# wifiaudiolink.net
KiCad netlist of a schematic drawn in EAGLE
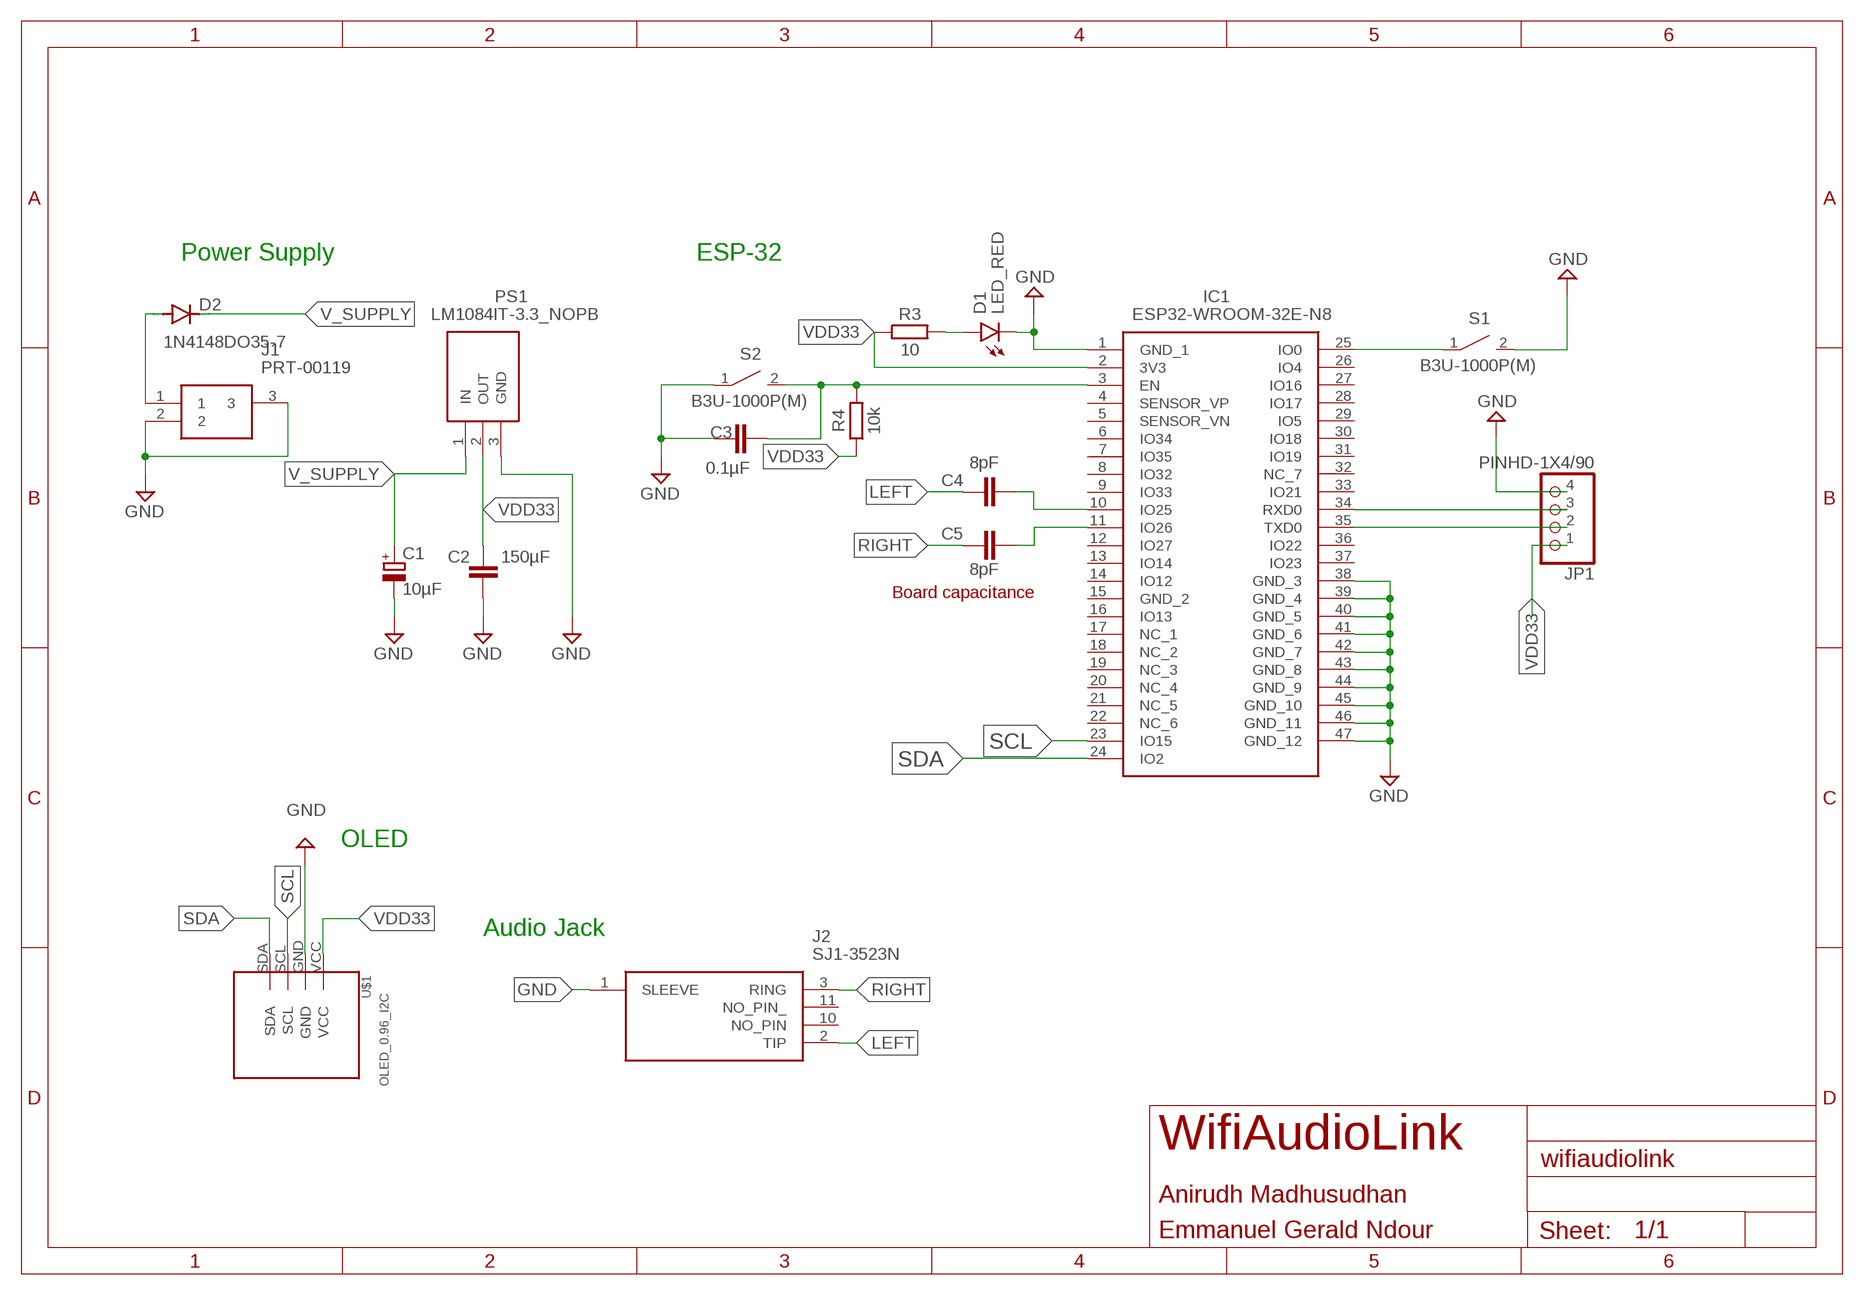
[diagram p0: schematic, sheet 1]

(export (version "E")
  (design (tool "Eeschema 10.0.6"))
  (components
    (comp (ref "C1")
      (value "10µF")
      (footprint "eagle-import:CAPPRD508W65D1000H1100B")
      (libsource (lib "eagle-import") (part "C-POLRADIAL-11MM-DIA_"))
    )
    (comp (ref "C2")
      (value "150µF")
      (footprint "eagle-import:CAPRD550W60D1025H1250B")
      (libsource (lib "eagle-import") (part "CRADIAL-12.5MM-DIA_"))
    )
    (comp (ref "C3")
      (value "0.1µF")
      (footprint "eagle-import:CAPC4532X135")
      (libsource (lib "eagle-import") (part "CCHIP-1812(4532-METRIC)_"))
    )
    (comp (ref "C4")
      (value "8pF")
      (footprint "eagle-import:CAPRD2261W240D5080H5555B")
      (libsource (lib "eagle-import") (part "Tutorial - Fusion 360_CRADIAL-55.5MM-DIA_"))
    )
    (comp (ref "C5")
      (value "8pF")
      (footprint "eagle-import:CAPRD2261W240D5080H5555B")
      (libsource (lib "eagle-import") (part "Tutorial - Fusion 360_CRADIAL-55.5MM-DIA_"))
    )
    (comp (ref "D1")
      (value "LED_RED")
      (footprint "eagle-import:LEDC3216X75N_FLAT-R")
      (libsource (lib "eagle-import") (part "CHIP-FLAT-R_1206"))
    )
    (comp (ref "D2")
      (value "1N4148DO35-7")
      (footprint "eagle-import:DO35-7")
      (libsource (lib "eagle-import") (part "1N4148DO35-7"))
    )
    (comp (ref "IC1")
      (value "ESP32-WROOM-32E-N8")
      (footprint "eagle-import:ESP32WROOM32EN8")
      (fields (field (name "MOUSER_PART_NUMBER") "356-ESP32WRM32E164PH"))
      (libsource (lib "eagle-import") (part "ESP32-WROOM-32E-N8"))
    )
    (comp (ref "J1")
      (value "PRT-00119")
      (footprint "eagle-import:PRT00119")
      (fields (field (name "MOUSER_PART_NUMBER") "474-PRT-00119"))
      (libsource (lib "eagle-import") (part "PRT-00119"))
    )
    (comp (ref "J2")
      (value "SJ1-3523N")
      (footprint "eagle-import:SJ13523N")
      (fields (field (name "MOUSER_PART_NUMBER") "490-SJ1-3523N"))
      (libsource (lib "eagle-import") (part "SJ1-3523N"))
    )
    (comp (ref "JP1")
      (value "PINHD-1X4/90")
      (footprint "eagle-import:1X04_90")
      (fields (field (name "MANUFACTURER") "Generic"))
      (libsource (lib "eagle-import") (part "PINHD-1X4/90"))
    )
    (comp (ref "PS1")
      (value "LM1084IT-3.3_NOPB")
      (footprint "eagle-import:TO254P470X1028X1955-3P")
      (fields
        (field (name "MANUFACTURER_PART_NUMBER") "LM1084IT-3.3/NOPB")
        (field (name "MOUSER_PART_NUMBER") "926-LM1084IT-3.3NOPB")
      )
      (libsource (lib "eagle-import") (part "LM1084IT-3.3_NOPB"))
    )
    (comp (ref "R3")
      (value "10")
      (footprint "eagle-import:RESC3216X70")
      (libsource (lib "eagle-import") (part "RCHIP-1206(3216-METRIC)_"))
    )
    (comp (ref "R4")
      (value "10k")
      (footprint "eagle-import:RESC3216X70")
      (libsource (lib "eagle-import") (part "RCHIP-1206(3216-METRIC)_"))
    )
    (comp (ref "S1")
      (value "B3U-1000P(M)")
      (footprint "eagle-import:B3U-1000P(M)")
      (fields (field (name "MANUFACTURER") "OMRON"))
      (libsource (lib "eagle-import") (part "B3U-X0001000P(M)B3U-1000P(M)"))
    )
    (comp (ref "S2")
      (value "B3U-1000P(M)")
      (footprint "eagle-import:B3U-1000P(M)")
      (fields (field (name "MANUFACTURER") "OMRON"))
      (libsource (lib "eagle-import") (part "B3U-X0001000P(M)B3U-1000P(M)"))
    )
    (comp (ref "U$1")
      (value "OLED_0.96_I2C")
      (footprint "eagle-import:OLED_0.96_I2C")
      (libsource (lib "eagle-import") (part "OLED_0.96_I2C"))
    )
  )
  (nets
    (net (code "1") (name "GND") (class "Default")
      (node (ref "C1") (pin "2") (pinfunction "-_2") (pintype "passive"))
      (node (ref "C2") (pin "2") (pinfunction "2_2") (pintype "passive"))
      (node (ref "C3") (pin "2") (pinfunction "2_2") (pintype "passive"))
      (node (ref "D1") (pin "C") (pinfunction "C_C") (pintype "passive"))
      (node (ref "IC1") (pin "1") (pinfunction "GND_1_1") (pintype "bidirectional"))
      (node (ref "IC1") (pin "38") (pinfunction "GND_3_38") (pintype "bidirectional"))
      (node (ref "IC1") (pin "39") (pinfunction "GND_4_39") (pintype "bidirectional"))
      (node (ref "IC1") (pin "40") (pinfunction "GND_5_40") (pintype "bidirectional"))
      (node (ref "IC1") (pin "41") (pinfunction "GND_6_41") (pintype "bidirectional"))
      (node (ref "IC1") (pin "42") (pinfunction "GND_7_42") (pintype "bidirectional"))
      (node (ref "IC1") (pin "43") (pinfunction "GND_8_43") (pintype "bidirectional"))
      (node (ref "IC1") (pin "44") (pinfunction "GND_9_44") (pintype "bidirectional"))
      (node (ref "IC1") (pin "45") (pinfunction "GND_10_45") (pintype "bidirectional"))
      (node (ref "IC1") (pin "46") (pinfunction "GND_11_46") (pintype "bidirectional"))
      (node (ref "IC1") (pin "47") (pinfunction "GND_12_47") (pintype "bidirectional"))
      (node (ref "J1") (pin "2") (pinfunction "2_2") (pintype "bidirectional"))
      (node (ref "J1") (pin "3") (pinfunction "3_3") (pintype "bidirectional"))
      (node (ref "J2") (pin "1") (pinfunction "SLEEVE_1") (pintype "bidirectional"))
      (node (ref "JP1") (pin "4") (pinfunction "4_4") (pintype "passive"))
      (node (ref "PS1") (pin "3") (pinfunction "GND_3") (pintype "power_in"))
      (node (ref "S1") (pin "2") (pinfunction "2_2") (pintype "bidirectional"))
      (node (ref "S2") (pin "1") (pinfunction "1_1") (pintype "bidirectional"))
      (node (ref "U$1") (pin "GND") (pinfunction "GND_GND") (pintype "bidirectional"))
    )
    (net (code "2") (name "LEFT") (class "Default")
      (node (ref "C4") (pin "1") (pinfunction "1_1") (pintype "passive"))
      (node (ref "J2") (pin "2") (pinfunction "TIP_2") (pintype "bidirectional"))
    )
    (net (code "3") (name "Net-(D1-PadA)") (class "Default")
      (node (ref "D1") (pin "A") (pinfunction "A_A") (pintype "passive"))
      (node (ref "R3") (pin "2") (pinfunction "2_2") (pintype "passive"))
    )
    (net (code "4") (name "Net-(D2-PadA)") (class "Default")
      (node (ref "D2") (pin "A") (pinfunction "A_A") (pintype "passive"))
      (node (ref "J1") (pin "1") (pinfunction "1_1") (pintype "bidirectional"))
    )
    (net (code "5") (name "Net-(IC1-EN)") (class "Default")
      (node (ref "C3") (pin "1") (pinfunction "1_1") (pintype "passive"))
      (node (ref "IC1") (pin "3") (pinfunction "EN_3") (pintype "bidirectional"))
      (node (ref "R4") (pin "2") (pinfunction "2_2") (pintype "passive"))
      (node (ref "S2") (pin "2") (pinfunction "2_2") (pintype "bidirectional"))
    )
    (net (code "6") (name "Net-(IC1-IO0)") (class "Default")
      (node (ref "IC1") (pin "25") (pinfunction "IO0_25") (pintype "bidirectional"))
      (node (ref "S1") (pin "1") (pinfunction "1_1") (pintype "bidirectional"))
    )
    (net (code "7") (name "Net-(IC1-IO25)") (class "Default")
      (node (ref "C4") (pin "2") (pinfunction "2_2") (pintype "passive"))
      (node (ref "IC1") (pin "10") (pinfunction "IO25_10") (pintype "bidirectional"))
    )
    (net (code "8") (name "Net-(IC1-IO26)") (class "Default")
      (node (ref "C5") (pin "2") (pinfunction "2_2") (pintype "passive"))
      (node (ref "IC1") (pin "11") (pinfunction "IO26_11") (pintype "bidirectional"))
    )
    (net (code "9") (name "Net-(IC1-RXD0)") (class "Default")
      (node (ref "IC1") (pin "34") (pinfunction "RXD0_34") (pintype "bidirectional"))
      (node (ref "JP1") (pin "3") (pinfunction "3_3") (pintype "passive"))
    )
    (net (code "10") (name "Net-(IC1-TXD0)") (class "Default")
      (node (ref "IC1") (pin "35") (pinfunction "TXD0_35") (pintype "bidirectional"))
      (node (ref "JP1") (pin "2") (pinfunction "2_2") (pintype "passive"))
    )
    (net (code "11") (name "RIGHT") (class "Default")
      (node (ref "C5") (pin "1") (pinfunction "1_1") (pintype "passive"))
      (node (ref "J2") (pin "3") (pinfunction "RING_3") (pintype "bidirectional"))
    )
    (net (code "12") (name "SCL") (class "Default")
      (node (ref "IC1") (pin "23") (pinfunction "IO15_23") (pintype "bidirectional"))
      (node (ref "U$1") (pin "SCL") (pinfunction "SCL_SCL") (pintype "bidirectional"))
    )
    (net (code "13") (name "SDA") (class "Default")
      (node (ref "IC1") (pin "24") (pinfunction "IO2_24") (pintype "bidirectional"))
      (node (ref "U$1") (pin "SDA") (pinfunction "SDA_SDA") (pintype "bidirectional"))
    )
    (net (code "14") (name "VDD33") (class "Default")
      (node (ref "C2") (pin "1") (pinfunction "1_1") (pintype "passive"))
      (node (ref "IC1") (pin "2") (pinfunction "3V3_2") (pintype "bidirectional"))
      (node (ref "JP1") (pin "1") (pinfunction "1_1") (pintype "passive"))
      (node (ref "PS1") (pin "2") (pinfunction "OUT_2") (pintype "output"))
      (node (ref "R3") (pin "1") (pinfunction "1_1") (pintype "passive"))
      (node (ref "R4") (pin "1") (pinfunction "1_1") (pintype "passive"))
      (node (ref "U$1") (pin "VCC") (pinfunction "VCC_VCC") (pintype "bidirectional"))
    )
    (net (code "15") (name "V_SUPPLY") (class "Default")
      (node (ref "C1") (pin "1") (pinfunction "+_1") (pintype "passive"))
      (node (ref "D2") (pin "C") (pinfunction "C_C") (pintype "passive"))
      (node (ref "PS1") (pin "1") (pinfunction "IN_1") (pintype "input"))
    )
    (net (code "16") (name "unconnected-(IC1-GND_2-Pad15)") (class "Default")
      (node (ref "IC1") (pin "15") (pinfunction "GND_2_15") (pintype "bidirectional"))
    )
    (net (code "17") (name "unconnected-(IC1-IO4-Pad26)") (class "Default")
      (node (ref "IC1") (pin "26") (pinfunction "IO4_26") (pintype "bidirectional"))
    )
    (net (code "18") (name "unconnected-(IC1-IO5-Pad29)") (class "Default")
      (node (ref "IC1") (pin "29") (pinfunction "IO5_29") (pintype "bidirectional"))
    )
    (net (code "19") (name "unconnected-(IC1-IO12-Pad14)") (class "Default")
      (node (ref "IC1") (pin "14") (pinfunction "IO12_14") (pintype "bidirectional"))
    )
    (net (code "20") (name "unconnected-(IC1-IO13-Pad16)") (class "Default")
      (node (ref "IC1") (pin "16") (pinfunction "IO13_16") (pintype "bidirectional"))
    )
    (net (code "21") (name "unconnected-(IC1-IO14-Pad13)") (class "Default")
      (node (ref "IC1") (pin "13") (pinfunction "IO14_13") (pintype "bidirectional"))
    )
    (net (code "22") (name "unconnected-(IC1-IO16-Pad27)") (class "Default")
      (node (ref "IC1") (pin "27") (pinfunction "IO16_27") (pintype "bidirectional"))
    )
    (net (code "23") (name "unconnected-(IC1-IO17-Pad28)") (class "Default")
      (node (ref "IC1") (pin "28") (pinfunction "IO17_28") (pintype "bidirectional"))
    )
    (net (code "24") (name "unconnected-(IC1-IO18-Pad30)") (class "Default")
      (node (ref "IC1") (pin "30") (pinfunction "IO18_30") (pintype "bidirectional"))
    )
    (net (code "25") (name "unconnected-(IC1-IO19-Pad31)") (class "Default")
      (node (ref "IC1") (pin "31") (pinfunction "IO19_31") (pintype "bidirectional"))
    )
    (net (code "26") (name "unconnected-(IC1-IO21-Pad33)") (class "Default")
      (node (ref "IC1") (pin "33") (pinfunction "IO21_33") (pintype "bidirectional"))
    )
    (net (code "27") (name "unconnected-(IC1-IO22-Pad36)") (class "Default")
      (node (ref "IC1") (pin "36") (pinfunction "IO22_36") (pintype "bidirectional"))
    )
    (net (code "28") (name "unconnected-(IC1-IO23-Pad37)") (class "Default")
      (node (ref "IC1") (pin "37") (pinfunction "IO23_37") (pintype "bidirectional"))
    )
    (net (code "29") (name "unconnected-(IC1-IO27-Pad12)") (class "Default")
      (node (ref "IC1") (pin "12") (pinfunction "IO27_12") (pintype "bidirectional"))
    )
    (net (code "30") (name "unconnected-(IC1-IO32-Pad8)") (class "Default")
      (node (ref "IC1") (pin "8") (pinfunction "IO32_8") (pintype "bidirectional"))
    )
    (net (code "31") (name "unconnected-(IC1-IO33-Pad9)") (class "Default")
      (node (ref "IC1") (pin "9") (pinfunction "IO33_9") (pintype "bidirectional"))
    )
    (net (code "32") (name "unconnected-(IC1-IO34-Pad6)") (class "Default")
      (node (ref "IC1") (pin "6") (pinfunction "IO34_6") (pintype "bidirectional"))
    )
    (net (code "33") (name "unconnected-(IC1-IO35-Pad7)") (class "Default")
      (node (ref "IC1") (pin "7") (pinfunction "IO35_7") (pintype "bidirectional"))
    )
    (net (code "34") (name "unconnected-(IC1-NC_1-Pad17)") (class "Default")
      (node (ref "IC1") (pin "17") (pinfunction "NC_1_17") (pintype "bidirectional"))
    )
    (net (code "35") (name "unconnected-(IC1-NC_2-Pad18)") (class "Default")
      (node (ref "IC1") (pin "18") (pinfunction "NC_2_18") (pintype "bidirectional"))
    )
    (net (code "36") (name "unconnected-(IC1-NC_3-Pad19)") (class "Default")
      (node (ref "IC1") (pin "19") (pinfunction "NC_3_19") (pintype "bidirectional"))
    )
    (net (code "37") (name "unconnected-(IC1-NC_4-Pad20)") (class "Default")
      (node (ref "IC1") (pin "20") (pinfunction "NC_4_20") (pintype "bidirectional"))
    )
    (net (code "38") (name "unconnected-(IC1-NC_5-Pad21)") (class "Default")
      (node (ref "IC1") (pin "21") (pinfunction "NC_5_21") (pintype "bidirectional"))
    )
    (net (code "39") (name "unconnected-(IC1-NC_6-Pad22)") (class "Default")
      (node (ref "IC1") (pin "22") (pinfunction "NC_6_22") (pintype "bidirectional"))
    )
    (net (code "40") (name "unconnected-(IC1-NC_7-Pad32)") (class "Default")
      (node (ref "IC1") (pin "32") (pinfunction "NC_7_32") (pintype "bidirectional"))
    )
    (net (code "41") (name "unconnected-(IC1-SENSOR_VN-Pad5)") (class "Default")
      (node (ref "IC1") (pin "5") (pinfunction "SENSOR_VN_5") (pintype "bidirectional"))
    )
    (net (code "42") (name "unconnected-(IC1-SENSOR_VP-Pad4)") (class "Default")
      (node (ref "IC1") (pin "4") (pinfunction "SENSOR_VP_4") (pintype "bidirectional"))
    )
    (net (code "43") (name "unconnected-(J2-NO_PIN-Pad10)") (class "Default")
      (node (ref "J2") (pin "10") (pinfunction "NO_PIN_10") (pintype "bidirectional"))
    )
    (net (code "44") (name "unconnected-(J2-NO_PIN_-Pad11)") (class "Default")
      (node (ref "J2") (pin "11") (pinfunction "NO_PIN__11") (pintype "bidirectional"))
    )
  )
)
